# VGA.net
KiCad netlist of a schematic drawn in Altium Designer
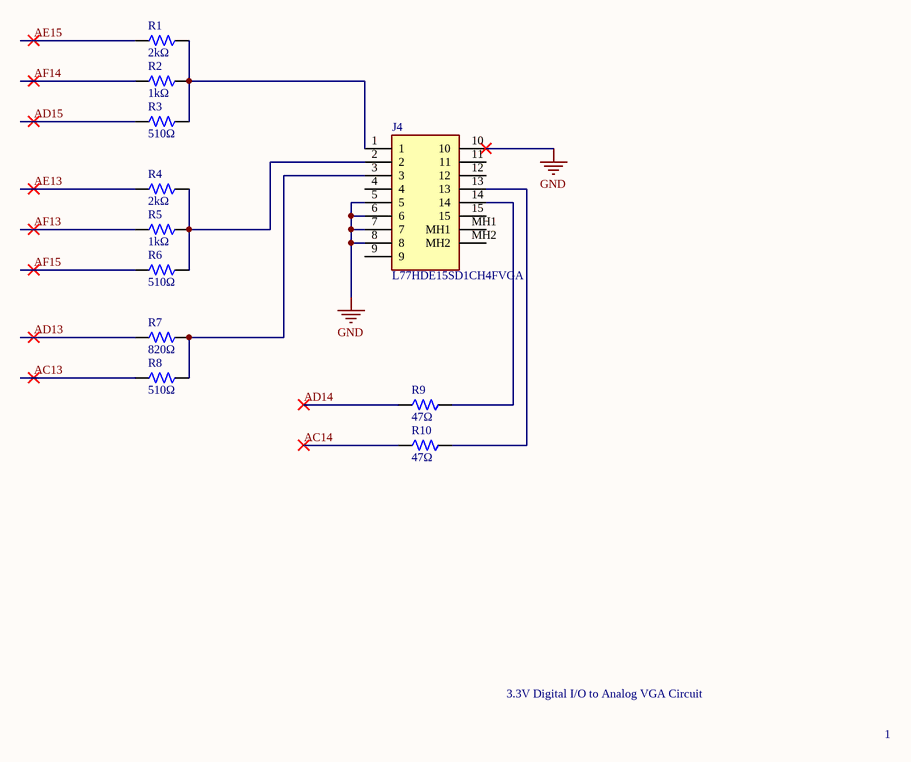
[diagram p0: VGA.SchDoc]

(export (version "E")
  (design (tool "Eeschema 10.0.6"))
  (components
    (comp (ref "J4")
      (value "L77HDE15SD1CH4FVGA")
      (footprint "SamacSys:L77HDE15SD1CH4FVGA")
      (description "Connector")
      (fields (field (name "MOUSER PART NUMBER") "523-7HDE15SD1CH4FVGA"))
      (libsource (lib "*") (part "L77HDE15SD1CH4FVGA"))
    )
    (comp (ref "R1")
      (value "0402WGF2001TCE")
      (footprint "RES-0402")
      (description "Resistor, 2kΩ, ±1%, 62.5mW, 50V, ±100ppm/℃, -55℃~+155℃, SMD 0402")
      (fields
        (field (name "MANUFACTURER") "Uniroyal")
        (field (name "JLCPCB PART NUMBER") "C4109")
        (field (name "RESISTANCE") "2kΩ")
      )
      (libsource (lib "jlcpcb_2025_04_resistors_basic") (part "0402WGF2001TCE"))
    )
    (comp (ref "R2")
      (value "0402WGF1001TCE")
      (footprint "RES-0402")
      (description "Resistor, 1kΩ, ±1%, 62.5mW, 50V, ±100ppm/℃, -55℃~+155℃, SMD 0402")
      (fields
        (field (name "MANUFACTURER") "Uniroyal")
        (field (name "JLCPCB PART NUMBER") "C11702")
        (field (name "RESISTANCE") "1kΩ")
      )
      (libsource (lib "jlcpcb_2025_04_resistors_basic") (part "0402WGF1001TCE"))
    )
    (comp (ref "R3")
      (value "0402WGF5100TCE")
      (footprint "RES-0402")
      (description "Resistor, 510Ω, ±1%, 62.5mW, 50V, ±100ppm/℃, -55℃~+155℃, SMD 0402")
      (fields
        (field (name "MANUFACTURER") "Uniroyal")
        (field (name "JLCPCB PART NUMBER") "C25123")
        (field (name "RESISTANCE") "510Ω")
      )
      (libsource (lib "jlcpcb_2025_04_resistors_basic") (part "0402WGF5100TCE"))
    )
    (comp (ref "R4")
      (value "0402WGF2001TCE")
      (footprint "RES-0402")
      (description "Resistor, 2kΩ, ±1%, 62.5mW, 50V, ±100ppm/℃, -55℃~+155℃, SMD 0402")
      (fields
        (field (name "MANUFACTURER") "Uniroyal")
        (field (name "JLCPCB PART NUMBER") "C4109")
        (field (name "RESISTANCE") "2kΩ")
      )
      (libsource (lib "jlcpcb_2025_04_resistors_basic") (part "0402WGF2001TCE"))
    )
    (comp (ref "R5")
      (value "0402WGF1001TCE")
      (footprint "RES-0402")
      (description "Resistor, 1kΩ, ±1%, 62.5mW, 50V, ±100ppm/℃, -55℃~+155℃, SMD 0402")
      (fields
        (field (name "MANUFACTURER") "Uniroyal")
        (field (name "JLCPCB PART NUMBER") "C11702")
        (field (name "RESISTANCE") "1kΩ")
      )
      (libsource (lib "jlcpcb_2025_04_resistors_basic") (part "0402WGF1001TCE"))
    )
    (comp (ref "R6")
      (value "0402WGF5100TCE")
      (footprint "RES-0402")
      (description "Resistor, 510Ω, ±1%, 62.5mW, 50V, ±100ppm/℃, -55℃~+155℃, SMD 0402")
      (fields
        (field (name "MANUFACTURER") "Uniroyal")
        (field (name "JLCPCB PART NUMBER") "C25123")
        (field (name "RESISTANCE") "510Ω")
      )
      (libsource (lib "jlcpcb_2025_04_resistors_basic") (part "0402WGF5100TCE"))
    )
    (comp (ref "R7")
      (value "0603WAF8200T5E")
      (footprint "RES-0603")
      (description "Resistor, 820Ω, ±1%, 100mW, 75V, ±100ppm/℃, -55℃~+155℃, SMD 0603")
      (fields
        (field (name "MANUFACTURER") "Uniroyal")
        (field (name "JLCPCB PART NUMBER") "C23253")
        (field (name "RESISTANCE") "820Ω")
      )
      (libsource (lib "jlcpcb_2025_04_resistors_basic") (part "0603WAF8200T5E"))
    )
    (comp (ref "R8")
      (value "0402WGF5100TCE")
      (footprint "RES-0402")
      (description "Resistor, 510Ω, ±1%, 62.5mW, 50V, ±100ppm/℃, -55℃~+155℃, SMD 0402")
      (fields
        (field (name "MANUFACTURER") "Uniroyal")
        (field (name "JLCPCB PART NUMBER") "C25123")
        (field (name "RESISTANCE") "510Ω")
      )
      (libsource (lib "jlcpcb_2025_04_resistors_basic") (part "0402WGF5100TCE"))
    )
    (comp (ref "R9")
      (value "0603WAF470JT5E")
      (footprint "RES-0603")
      (description "Resistor, 47Ω, ±1%, 100mW, 75V, ±100ppm/℃, -55℃~+155℃, SMD 0603")
      (fields
        (field (name "MANUFACTURER") "Uniroyal")
        (field (name "JLCPCB PART NUMBER") "C23182")
        (field (name "RESISTANCE") "47Ω")
      )
      (libsource (lib "jlcpcb_2025_04_resistors_basic") (part "0603WAF470JT5E"))
    )
    (comp (ref "R10")
      (value "0603WAF470JT5E")
      (footprint "RES-0603")
      (description "Resistor, 47Ω, ±1%, 100mW, 75V, ±100ppm/℃, -55℃~+155℃, SMD 0603")
      (fields
        (field (name "MANUFACTURER") "Uniroyal")
        (field (name "JLCPCB PART NUMBER") "C23182")
        (field (name "RESISTANCE") "47Ω")
      )
      (libsource (lib "jlcpcb_2025_04_resistors_basic") (part "0603WAF470JT5E"))
    )
  )
  (nets
    (net (code "2") (name "/AC13") (class "Default")
      (node (ref "R8") (pin "1") (pinfunction "1_1") (pintype "passive"))
    )
    (net (code "4") (name "/AC14") (class "Default")
      (node (ref "R10") (pin "1") (pinfunction "1_1") (pintype "passive+no_connect"))
    )
    (net (code "11") (name "/AD13") (class "Default")
      (node (ref "R7") (pin "1") (pinfunction "1_1") (pintype "passive"))
    )
    (net (code "12") (name "/AD14") (class "Default")
      (node (ref "R9") (pin "1") (pinfunction "1_1") (pintype "passive+no_connect"))
    )
    (net (code "13") (name "/AD15") (class "Default")
      (node (ref "R3") (pin "1") (pinfunction "1_1") (pintype "passive"))
    )
    (net (code "14") (name "/AE13") (class "Default")
      (node (ref "R4") (pin "1") (pinfunction "1_1") (pintype "passive"))
    )
    (net (code "15") (name "/AE15") (class "Default")
      (node (ref "R1") (pin "1") (pinfunction "1_1") (pintype "passive"))
    )
    (net (code "16") (name "/AF13") (class "Default")
      (node (ref "R5") (pin "1") (pinfunction "1_1") (pintype "passive"))
    )
    (net (code "17") (name "/AF14") (class "Default")
      (node (ref "R2") (pin "1") (pinfunction "1_1") (pintype "passive"))
    )
    (net (code "18") (name "/AF15") (class "Default")
      (node (ref "R6") (pin "1") (pinfunction "1_1") (pintype "passive"))
    )
    (net (code "19") (name "GND") (class "Default")
      (node (ref "J4") (pin "10") (pinfunction "10_10") (pintype "passive"))
      (node (ref "J4") (pin "5") (pinfunction "5_5") (pintype "passive"))
      (node (ref "J4") (pin "6") (pinfunction "6_6") (pintype "passive"))
      (node (ref "J4") (pin "7") (pinfunction "7_7") (pintype "passive"))
      (node (ref "J4") (pin "8") (pinfunction "8_8") (pintype "passive"))
    )
    (net (code "20") (name "Net-(J4-Pad1)") (class "Default")
      (node (ref "J4") (pin "1") (pinfunction "1_1") (pintype "passive"))
      (node (ref "R1") (pin "2") (pinfunction "2_2") (pintype "passive"))
      (node (ref "R2") (pin "2") (pinfunction "2_2") (pintype "passive"))
      (node (ref "R3") (pin "2") (pinfunction "2_2") (pintype "passive"))
    )
    (net (code "21") (name "Net-(J4-Pad2)") (class "Default")
      (node (ref "J4") (pin "2") (pinfunction "2_2") (pintype "passive"))
      (node (ref "R4") (pin "2") (pinfunction "2_2") (pintype "passive"))
      (node (ref "R5") (pin "2") (pinfunction "2_2") (pintype "passive"))
      (node (ref "R6") (pin "2") (pinfunction "2_2") (pintype "passive"))
    )
    (net (code "22") (name "Net-(J4-Pad3)") (class "Default")
      (node (ref "J4") (pin "3") (pinfunction "3_3") (pintype "passive"))
      (node (ref "R7") (pin "2") (pinfunction "2_2") (pintype "passive"))
      (node (ref "R8") (pin "2") (pinfunction "2_2") (pintype "passive"))
    )
    (net (code "23") (name "Net-(J4-Pad13)") (class "Default")
      (node (ref "J4") (pin "13") (pinfunction "13_13") (pintype "passive"))
      (node (ref "R10") (pin "2") (pinfunction "2_2") (pintype "passive"))
    )
    (net (code "24") (name "Net-(J4-Pad14)") (class "Default")
      (node (ref "J4") (pin "14") (pinfunction "14_14") (pintype "passive"))
      (node (ref "R9") (pin "2") (pinfunction "2_2") (pintype "passive"))
    )
    (net (code "25") (name "unconnected-(J4-Pad4)") (class "Default")
      (node (ref "J4") (pin "4") (pinfunction "4_4") (pintype "passive"))
    )
    (net (code "26") (name "unconnected-(J4-Pad9)") (class "Default")
      (node (ref "J4") (pin "9") (pinfunction "9_9") (pintype "passive"))
    )
    (net (code "27") (name "unconnected-(J4-Pad11)") (class "Default")
      (node (ref "J4") (pin "11") (pinfunction "11_11") (pintype "passive"))
    )
    (net (code "28") (name "unconnected-(J4-Pad12)") (class "Default")
      (node (ref "J4") (pin "12") (pinfunction "12_12") (pintype "passive"))
    )
    (net (code "29") (name "unconnected-(J4-Pad15)") (class "Default")
      (node (ref "J4") (pin "15") (pinfunction "15_15") (pintype "passive"))
    )
    (net (code "30") (name "unconnected-(J4-PadMH1)") (class "Default")
      (node (ref "J4") (pin "MH1") (pinfunction "MH1_MH1") (pintype "passive"))
    )
    (net (code "31") (name "unconnected-(J4-PadMH2)") (class "Default")
      (node (ref "J4") (pin "MH2") (pinfunction "MH2_MH2") (pintype "passive"))
    )
  )
)
